# Power_Bus.net
KiCad netlist of a schematic drawn in EAGLE
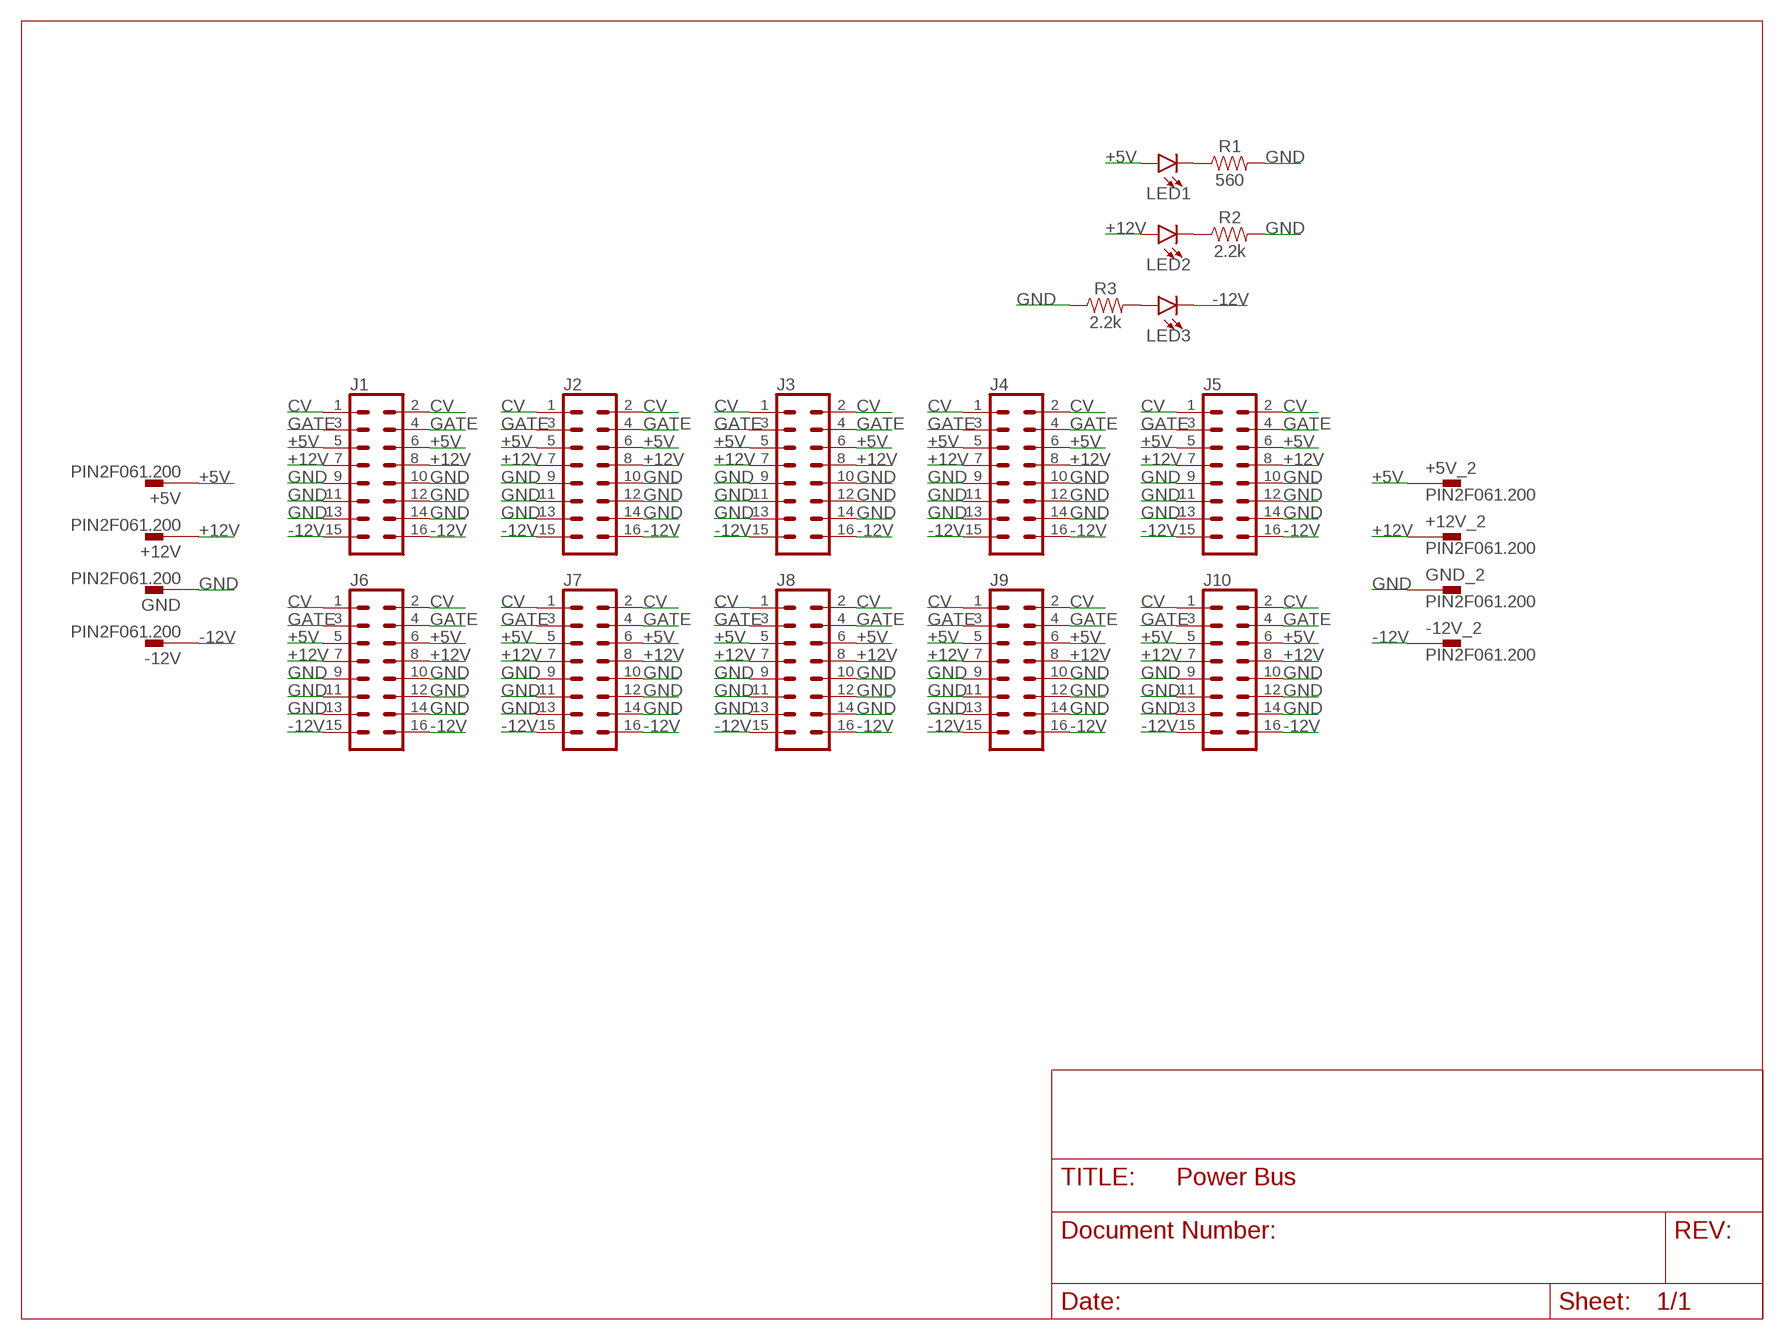
[diagram p0: schematic, sheet 1]

(export (version "E")
  (design (tool "Eeschema 10.0.6"))
  (components
    (comp (ref "+5V")
      (value "PIN2F061.200")
      (footprint "eagle-import:F061.200")
      (libsource (lib "eagle-import") (part "PIN2F061.200"))
    )
    (comp (ref "+5V_2")
      (value "PIN2F061.200")
      (footprint "eagle-import:F061.200")
      (libsource (lib "eagle-import") (part "PIN2F061.200"))
    )
    (comp (ref "+12V")
      (value "PIN2F061.200")
      (footprint "eagle-import:F061.200")
      (libsource (lib "eagle-import") (part "PIN2F061.200"))
    )
    (comp (ref "+12V_2")
      (value "PIN2F061.200")
      (footprint "eagle-import:F061.200")
      (libsource (lib "eagle-import") (part "PIN2F061.200"))
    )
    (comp (ref "-12V")
      (value "PIN2F061.200")
      (footprint "eagle-import:F061.200")
      (libsource (lib "eagle-import") (part "PIN2F061.200"))
    )
    (comp (ref "-12V_2")
      (value "PIN2F061.200")
      (footprint "eagle-import:F061.200")
      (libsource (lib "eagle-import") (part "PIN2F061.200"))
    )
    (comp (ref "GND")
      (value "PIN2F061.200")
      (footprint "eagle-import:F061.200")
      (libsource (lib "eagle-import") (part "PIN2F061.200"))
    )
    (comp (ref "GND_2")
      (value "PIN2F061.200")
      (footprint "eagle-import:F061.200")
      (libsource (lib "eagle-import") (part "PIN2F061.200"))
    )
    (comp (ref "J1")
      (value "CONN_08X2_HEADER")
      (footprint "eagle-import:2X8")
      (libsource (lib "eagle-import") (part "CONN_08X2_HEADER"))
    )
    (comp (ref "J2")
      (value "CONN_08X2_HEADER")
      (footprint "eagle-import:2X8")
      (libsource (lib "eagle-import") (part "CONN_08X2_HEADER"))
    )
    (comp (ref "J3")
      (value "CONN_08X2_HEADER")
      (footprint "eagle-import:2X8")
      (libsource (lib "eagle-import") (part "CONN_08X2_HEADER"))
    )
    (comp (ref "J4")
      (value "CONN_08X2_HEADER")
      (footprint "eagle-import:2X8")
      (libsource (lib "eagle-import") (part "CONN_08X2_HEADER"))
    )
    (comp (ref "J5")
      (value "CONN_08X2_HEADER")
      (footprint "eagle-import:2X8")
      (libsource (lib "eagle-import") (part "CONN_08X2_HEADER"))
    )
    (comp (ref "J6")
      (value "CONN_08X2_HEADER")
      (footprint "eagle-import:2X8")
      (libsource (lib "eagle-import") (part "CONN_08X2_HEADER"))
    )
    (comp (ref "J7")
      (value "CONN_08X2_HEADER")
      (footprint "eagle-import:2X8")
      (libsource (lib "eagle-import") (part "CONN_08X2_HEADER"))
    )
    (comp (ref "J8")
      (value "CONN_08X2_HEADER")
      (footprint "eagle-import:2X8")
      (libsource (lib "eagle-import") (part "CONN_08X2_HEADER"))
    )
    (comp (ref "J9")
      (value "CONN_08X2_HEADER")
      (footprint "eagle-import:2X8")
      (libsource (lib "eagle-import") (part "CONN_08X2_HEADER"))
    )
    (comp (ref "J10")
      (value "CONN_08X2_HEADER")
      (footprint "eagle-import:2X8")
      (libsource (lib "eagle-import") (part "CONN_08X2_HEADER"))
    )
    (comp (ref "LED1")
      (value "LED3MM")
      (footprint "eagle-import:LED_3MM")
      (libsource (lib "eagle-import") (part "LED3MM"))
    )
    (comp (ref "LED2")
      (value "LED3MM")
      (footprint "eagle-import:LED_3MM")
      (libsource (lib "eagle-import") (part "LED3MM"))
    )
    (comp (ref "LED3")
      (value "LED3MM")
      (footprint "eagle-import:LED_3MM")
      (libsource (lib "eagle-import") (part "LED3MM"))
    )
    (comp (ref "R1")
      (value "560")
      (footprint "eagle-import:AXIAL-0.3")
      (libsource (lib "eagle-import") (part "1KOHM-HORIZ-1/4W-5%"))
    )
    (comp (ref "R2")
      (value "2.2k")
      (footprint "eagle-import:AXIAL-0.3")
      (libsource (lib "eagle-import") (part "1KOHM-HORIZ-1/4W-5%"))
    )
    (comp (ref "R3")
      (value "2.2k")
      (footprint "eagle-import:AXIAL-0.3")
      (libsource (lib "eagle-import") (part "1KOHM-HORIZ-1/4W-5%"))
    )
  )
  (nets
    (net (code "1") (name "/+5V") (class "Default")
      (node (ref "+5V") (pin "1A") (pinfunction "1_1A") (pintype "passive"))
      (node (ref "+5V") (pin "1B") (pinfunction "1_1B") (pintype "passive"))
      (node (ref "+5V_2") (pin "1A") (pinfunction "1_1A") (pintype "passive"))
      (node (ref "+5V_2") (pin "1B") (pinfunction "1_1B") (pintype "passive"))
      (node (ref "J1") (pin "5") (pinfunction "5_5") (pintype "passive"))
      (node (ref "J1") (pin "6") (pinfunction "6_6") (pintype "passive"))
      (node (ref "J10") (pin "5") (pinfunction "5_5") (pintype "passive"))
      (node (ref "J10") (pin "6") (pinfunction "6_6") (pintype "passive"))
      (node (ref "J2") (pin "5") (pinfunction "5_5") (pintype "passive"))
      (node (ref "J2") (pin "6") (pinfunction "6_6") (pintype "passive"))
      (node (ref "J3") (pin "5") (pinfunction "5_5") (pintype "passive"))
      (node (ref "J3") (pin "6") (pinfunction "6_6") (pintype "passive"))
      (node (ref "J4") (pin "5") (pinfunction "5_5") (pintype "passive"))
      (node (ref "J4") (pin "6") (pinfunction "6_6") (pintype "passive"))
      (node (ref "J5") (pin "5") (pinfunction "5_5") (pintype "passive"))
      (node (ref "J5") (pin "6") (pinfunction "6_6") (pintype "passive"))
      (node (ref "J6") (pin "5") (pinfunction "5_5") (pintype "passive"))
      (node (ref "J6") (pin "6") (pinfunction "6_6") (pintype "passive"))
      (node (ref "J7") (pin "5") (pinfunction "5_5") (pintype "passive"))
      (node (ref "J7") (pin "6") (pinfunction "6_6") (pintype "passive"))
      (node (ref "J8") (pin "5") (pinfunction "5_5") (pintype "passive"))
      (node (ref "J8") (pin "6") (pinfunction "6_6") (pintype "passive"))
      (node (ref "J9") (pin "5") (pinfunction "5_5") (pintype "passive"))
      (node (ref "J9") (pin "6") (pinfunction "6_6") (pintype "passive"))
      (node (ref "LED1") (pin "A") (pinfunction "A_A") (pintype "passive"))
    )
    (net (code "2") (name "/+12V") (class "Default")
      (node (ref "+12V") (pin "1A") (pinfunction "1_1A") (pintype "passive"))
      (node (ref "+12V") (pin "1B") (pinfunction "1_1B") (pintype "passive"))
      (node (ref "+12V_2") (pin "1A") (pinfunction "1_1A") (pintype "passive"))
      (node (ref "+12V_2") (pin "1B") (pinfunction "1_1B") (pintype "passive"))
      (node (ref "J1") (pin "7") (pinfunction "7_7") (pintype "passive"))
      (node (ref "J1") (pin "8") (pinfunction "8_8") (pintype "passive"))
      (node (ref "J10") (pin "7") (pinfunction "7_7") (pintype "passive"))
      (node (ref "J10") (pin "8") (pinfunction "8_8") (pintype "passive"))
      (node (ref "J2") (pin "7") (pinfunction "7_7") (pintype "passive"))
      (node (ref "J2") (pin "8") (pinfunction "8_8") (pintype "passive"))
      (node (ref "J3") (pin "7") (pinfunction "7_7") (pintype "passive"))
      (node (ref "J3") (pin "8") (pinfunction "8_8") (pintype "passive"))
      (node (ref "J4") (pin "7") (pinfunction "7_7") (pintype "passive"))
      (node (ref "J4") (pin "8") (pinfunction "8_8") (pintype "passive"))
      (node (ref "J5") (pin "7") (pinfunction "7_7") (pintype "passive"))
      (node (ref "J5") (pin "8") (pinfunction "8_8") (pintype "passive"))
      (node (ref "J6") (pin "7") (pinfunction "7_7") (pintype "passive"))
      (node (ref "J6") (pin "8") (pinfunction "8_8") (pintype "passive"))
      (node (ref "J7") (pin "7") (pinfunction "7_7") (pintype "passive"))
      (node (ref "J7") (pin "8") (pinfunction "8_8") (pintype "passive"))
      (node (ref "J8") (pin "7") (pinfunction "7_7") (pintype "passive"))
      (node (ref "J8") (pin "8") (pinfunction "8_8") (pintype "passive"))
      (node (ref "J9") (pin "7") (pinfunction "7_7") (pintype "passive"))
      (node (ref "J9") (pin "8") (pinfunction "8_8") (pintype "passive"))
      (node (ref "LED2") (pin "A") (pinfunction "A_A") (pintype "passive"))
    )
    (net (code "3") (name "/-12V") (class "Default")
      (node (ref "-12V") (pin "1A") (pinfunction "1_1A") (pintype "passive"))
      (node (ref "-12V") (pin "1B") (pinfunction "1_1B") (pintype "passive"))
      (node (ref "-12V_2") (pin "1A") (pinfunction "1_1A") (pintype "passive"))
      (node (ref "-12V_2") (pin "1B") (pinfunction "1_1B") (pintype "passive"))
      (node (ref "J1") (pin "15") (pinfunction "15_15") (pintype "passive"))
      (node (ref "J1") (pin "16") (pinfunction "16_16") (pintype "passive"))
      (node (ref "J10") (pin "15") (pinfunction "15_15") (pintype "passive"))
      (node (ref "J10") (pin "16") (pinfunction "16_16") (pintype "passive"))
      (node (ref "J2") (pin "15") (pinfunction "15_15") (pintype "passive"))
      (node (ref "J2") (pin "16") (pinfunction "16_16") (pintype "passive"))
      (node (ref "J3") (pin "15") (pinfunction "15_15") (pintype "passive"))
      (node (ref "J3") (pin "16") (pinfunction "16_16") (pintype "passive"))
      (node (ref "J4") (pin "15") (pinfunction "15_15") (pintype "passive"))
      (node (ref "J4") (pin "16") (pinfunction "16_16") (pintype "passive"))
      (node (ref "J5") (pin "15") (pinfunction "15_15") (pintype "passive"))
      (node (ref "J5") (pin "16") (pinfunction "16_16") (pintype "passive"))
      (node (ref "J6") (pin "15") (pinfunction "15_15") (pintype "passive"))
      (node (ref "J6") (pin "16") (pinfunction "16_16") (pintype "passive"))
      (node (ref "J7") (pin "15") (pinfunction "15_15") (pintype "passive"))
      (node (ref "J7") (pin "16") (pinfunction "16_16") (pintype "passive"))
      (node (ref "J8") (pin "15") (pinfunction "15_15") (pintype "passive"))
      (node (ref "J8") (pin "16") (pinfunction "16_16") (pintype "passive"))
      (node (ref "J9") (pin "15") (pinfunction "15_15") (pintype "passive"))
      (node (ref "J9") (pin "16") (pinfunction "16_16") (pintype "passive"))
      (node (ref "LED3") (pin "K") (pinfunction "C_K") (pintype "passive"))
    )
    (net (code "4") (name "/CV") (class "Default")
      (node (ref "J1") (pin "1") (pinfunction "1_1") (pintype "passive"))
      (node (ref "J1") (pin "2") (pinfunction "2_2") (pintype "passive"))
      (node (ref "J10") (pin "1") (pinfunction "1_1") (pintype "passive"))
      (node (ref "J10") (pin "2") (pinfunction "2_2") (pintype "passive"))
      (node (ref "J2") (pin "1") (pinfunction "1_1") (pintype "passive"))
      (node (ref "J2") (pin "2") (pinfunction "2_2") (pintype "passive"))
      (node (ref "J3") (pin "1") (pinfunction "1_1") (pintype "passive"))
      (node (ref "J3") (pin "2") (pinfunction "2_2") (pintype "passive"))
      (node (ref "J4") (pin "1") (pinfunction "1_1") (pintype "passive"))
      (node (ref "J4") (pin "2") (pinfunction "2_2") (pintype "passive"))
      (node (ref "J5") (pin "1") (pinfunction "1_1") (pintype "passive"))
      (node (ref "J5") (pin "2") (pinfunction "2_2") (pintype "passive"))
      (node (ref "J6") (pin "1") (pinfunction "1_1") (pintype "passive"))
      (node (ref "J6") (pin "2") (pinfunction "2_2") (pintype "passive"))
      (node (ref "J7") (pin "1") (pinfunction "1_1") (pintype "passive"))
      (node (ref "J7") (pin "2") (pinfunction "2_2") (pintype "passive"))
      (node (ref "J8") (pin "1") (pinfunction "1_1") (pintype "passive"))
      (node (ref "J8") (pin "2") (pinfunction "2_2") (pintype "passive"))
      (node (ref "J9") (pin "1") (pinfunction "1_1") (pintype "passive"))
      (node (ref "J9") (pin "2") (pinfunction "2_2") (pintype "passive"))
    )
    (net (code "5") (name "/GATE") (class "Default")
      (node (ref "J1") (pin "3") (pinfunction "3_3") (pintype "passive"))
      (node (ref "J1") (pin "4") (pinfunction "4_4") (pintype "passive"))
      (node (ref "J10") (pin "3") (pinfunction "3_3") (pintype "passive"))
      (node (ref "J10") (pin "4") (pinfunction "4_4") (pintype "passive"))
      (node (ref "J2") (pin "3") (pinfunction "3_3") (pintype "passive"))
      (node (ref "J2") (pin "4") (pinfunction "4_4") (pintype "passive"))
      (node (ref "J3") (pin "3") (pinfunction "3_3") (pintype "passive"))
      (node (ref "J3") (pin "4") (pinfunction "4_4") (pintype "passive"))
      (node (ref "J4") (pin "3") (pinfunction "3_3") (pintype "passive"))
      (node (ref "J4") (pin "4") (pinfunction "4_4") (pintype "passive"))
      (node (ref "J5") (pin "3") (pinfunction "3_3") (pintype "passive"))
      (node (ref "J5") (pin "4") (pinfunction "4_4") (pintype "passive"))
      (node (ref "J6") (pin "3") (pinfunction "3_3") (pintype "passive"))
      (node (ref "J6") (pin "4") (pinfunction "4_4") (pintype "passive"))
      (node (ref "J7") (pin "3") (pinfunction "3_3") (pintype "passive"))
      (node (ref "J7") (pin "4") (pinfunction "4_4") (pintype "passive"))
      (node (ref "J8") (pin "3") (pinfunction "3_3") (pintype "passive"))
      (node (ref "J8") (pin "4") (pinfunction "4_4") (pintype "passive"))
      (node (ref "J9") (pin "3") (pinfunction "3_3") (pintype "passive"))
      (node (ref "J9") (pin "4") (pinfunction "4_4") (pintype "passive"))
    )
    (net (code "6") (name "/GND") (class "Default")
      (node (ref "GND") (pin "1A") (pinfunction "1_1A") (pintype "passive"))
      (node (ref "GND") (pin "1B") (pinfunction "1_1B") (pintype "passive"))
      (node (ref "GND_2") (pin "1A") (pinfunction "1_1A") (pintype "passive"))
      (node (ref "GND_2") (pin "1B") (pinfunction "1_1B") (pintype "passive"))
      (node (ref "J1") (pin "10") (pinfunction "10_10") (pintype "passive"))
      (node (ref "J1") (pin "11") (pinfunction "11_11") (pintype "passive"))
      (node (ref "J1") (pin "12") (pinfunction "12_12") (pintype "passive"))
      (node (ref "J1") (pin "13") (pinfunction "13_13") (pintype "passive"))
      (node (ref "J1") (pin "14") (pinfunction "14_14") (pintype "passive"))
      (node (ref "J1") (pin "9") (pinfunction "9_9") (pintype "passive"))
      (node (ref "J10") (pin "10") (pinfunction "10_10") (pintype "passive"))
      (node (ref "J10") (pin "11") (pinfunction "11_11") (pintype "passive"))
      (node (ref "J10") (pin "12") (pinfunction "12_12") (pintype "passive"))
      (node (ref "J10") (pin "13") (pinfunction "13_13") (pintype "passive"))
      (node (ref "J10") (pin "14") (pinfunction "14_14") (pintype "passive"))
      (node (ref "J10") (pin "9") (pinfunction "9_9") (pintype "passive"))
      (node (ref "J2") (pin "10") (pinfunction "10_10") (pintype "passive"))
      (node (ref "J2") (pin "11") (pinfunction "11_11") (pintype "passive"))
      (node (ref "J2") (pin "12") (pinfunction "12_12") (pintype "passive"))
      (node (ref "J2") (pin "13") (pinfunction "13_13") (pintype "passive"))
      (node (ref "J2") (pin "14") (pinfunction "14_14") (pintype "passive"))
      (node (ref "J2") (pin "9") (pinfunction "9_9") (pintype "passive"))
      (node (ref "J3") (pin "10") (pinfunction "10_10") (pintype "passive"))
      (node (ref "J3") (pin "11") (pinfunction "11_11") (pintype "passive"))
      (node (ref "J3") (pin "12") (pinfunction "12_12") (pintype "passive"))
      (node (ref "J3") (pin "13") (pinfunction "13_13") (pintype "passive"))
      (node (ref "J3") (pin "14") (pinfunction "14_14") (pintype "passive"))
      (node (ref "J3") (pin "9") (pinfunction "9_9") (pintype "passive"))
      (node (ref "J4") (pin "10") (pinfunction "10_10") (pintype "passive"))
      (node (ref "J4") (pin "11") (pinfunction "11_11") (pintype "passive"))
      (node (ref "J4") (pin "12") (pinfunction "12_12") (pintype "passive"))
      (node (ref "J4") (pin "13") (pinfunction "13_13") (pintype "passive"))
      (node (ref "J4") (pin "14") (pinfunction "14_14") (pintype "passive"))
      (node (ref "J4") (pin "9") (pinfunction "9_9") (pintype "passive"))
      (node (ref "J5") (pin "10") (pinfunction "10_10") (pintype "passive"))
      (node (ref "J5") (pin "11") (pinfunction "11_11") (pintype "passive"))
      (node (ref "J5") (pin "12") (pinfunction "12_12") (pintype "passive"))
      (node (ref "J5") (pin "13") (pinfunction "13_13") (pintype "passive"))
      (node (ref "J5") (pin "14") (pinfunction "14_14") (pintype "passive"))
      (node (ref "J5") (pin "9") (pinfunction "9_9") (pintype "passive"))
      (node (ref "J6") (pin "10") (pinfunction "10_10") (pintype "passive"))
      (node (ref "J6") (pin "11") (pinfunction "11_11") (pintype "passive"))
      (node (ref "J6") (pin "12") (pinfunction "12_12") (pintype "passive"))
      (node (ref "J6") (pin "13") (pinfunction "13_13") (pintype "passive"))
      (node (ref "J6") (pin "14") (pinfunction "14_14") (pintype "passive"))
      (node (ref "J6") (pin "9") (pinfunction "9_9") (pintype "passive"))
      (node (ref "J7") (pin "10") (pinfunction "10_10") (pintype "passive"))
      (node (ref "J7") (pin "11") (pinfunction "11_11") (pintype "passive"))
      (node (ref "J7") (pin "12") (pinfunction "12_12") (pintype "passive"))
      (node (ref "J7") (pin "13") (pinfunction "13_13") (pintype "passive"))
      (node (ref "J7") (pin "14") (pinfunction "14_14") (pintype "passive"))
      (node (ref "J7") (pin "9") (pinfunction "9_9") (pintype "passive"))
      (node (ref "J8") (pin "10") (pinfunction "10_10") (pintype "passive"))
      (node (ref "J8") (pin "11") (pinfunction "11_11") (pintype "passive"))
      (node (ref "J8") (pin "12") (pinfunction "12_12") (pintype "passive"))
      (node (ref "J8") (pin "13") (pinfunction "13_13") (pintype "passive"))
      (node (ref "J8") (pin "14") (pinfunction "14_14") (pintype "passive"))
      (node (ref "J8") (pin "9") (pinfunction "9_9") (pintype "passive"))
      (node (ref "J9") (pin "10") (pinfunction "10_10") (pintype "passive"))
      (node (ref "J9") (pin "11") (pinfunction "11_11") (pintype "passive"))
      (node (ref "J9") (pin "12") (pinfunction "12_12") (pintype "passive"))
      (node (ref "J9") (pin "13") (pinfunction "13_13") (pintype "passive"))
      (node (ref "J9") (pin "14") (pinfunction "14_14") (pintype "passive"))
      (node (ref "J9") (pin "9") (pinfunction "9_9") (pintype "passive"))
      (node (ref "R1") (pin "P$2") (pinfunction "2_P$2") (pintype "passive"))
      (node (ref "R2") (pin "P$2") (pinfunction "2_P$2") (pintype "passive"))
      (node (ref "R3") (pin "P$1") (pinfunction "1_P$1") (pintype "passive"))
    )
    (net (code "7") (name "Net-(LED1-C)") (class "Default")
      (node (ref "LED1") (pin "K") (pinfunction "C_K") (pintype "passive"))
      (node (ref "R1") (pin "P$1") (pinfunction "1_P$1") (pintype "passive"))
    )
    (net (code "8") (name "Net-(LED2-C)") (class "Default")
      (node (ref "LED2") (pin "K") (pinfunction "C_K") (pintype "passive"))
      (node (ref "R2") (pin "P$1") (pinfunction "1_P$1") (pintype "passive"))
    )
    (net (code "9") (name "Net-(R3-2)") (class "Default")
      (node (ref "LED3") (pin "A") (pinfunction "A_A") (pintype "passive"))
      (node (ref "R3") (pin "P$2") (pinfunction "2_P$2") (pintype "passive"))
    )
  )
)
